# SCH_Workshop-components_2025-10-19_2.net
KiCad netlist of a schematic drawn in EasyEDA
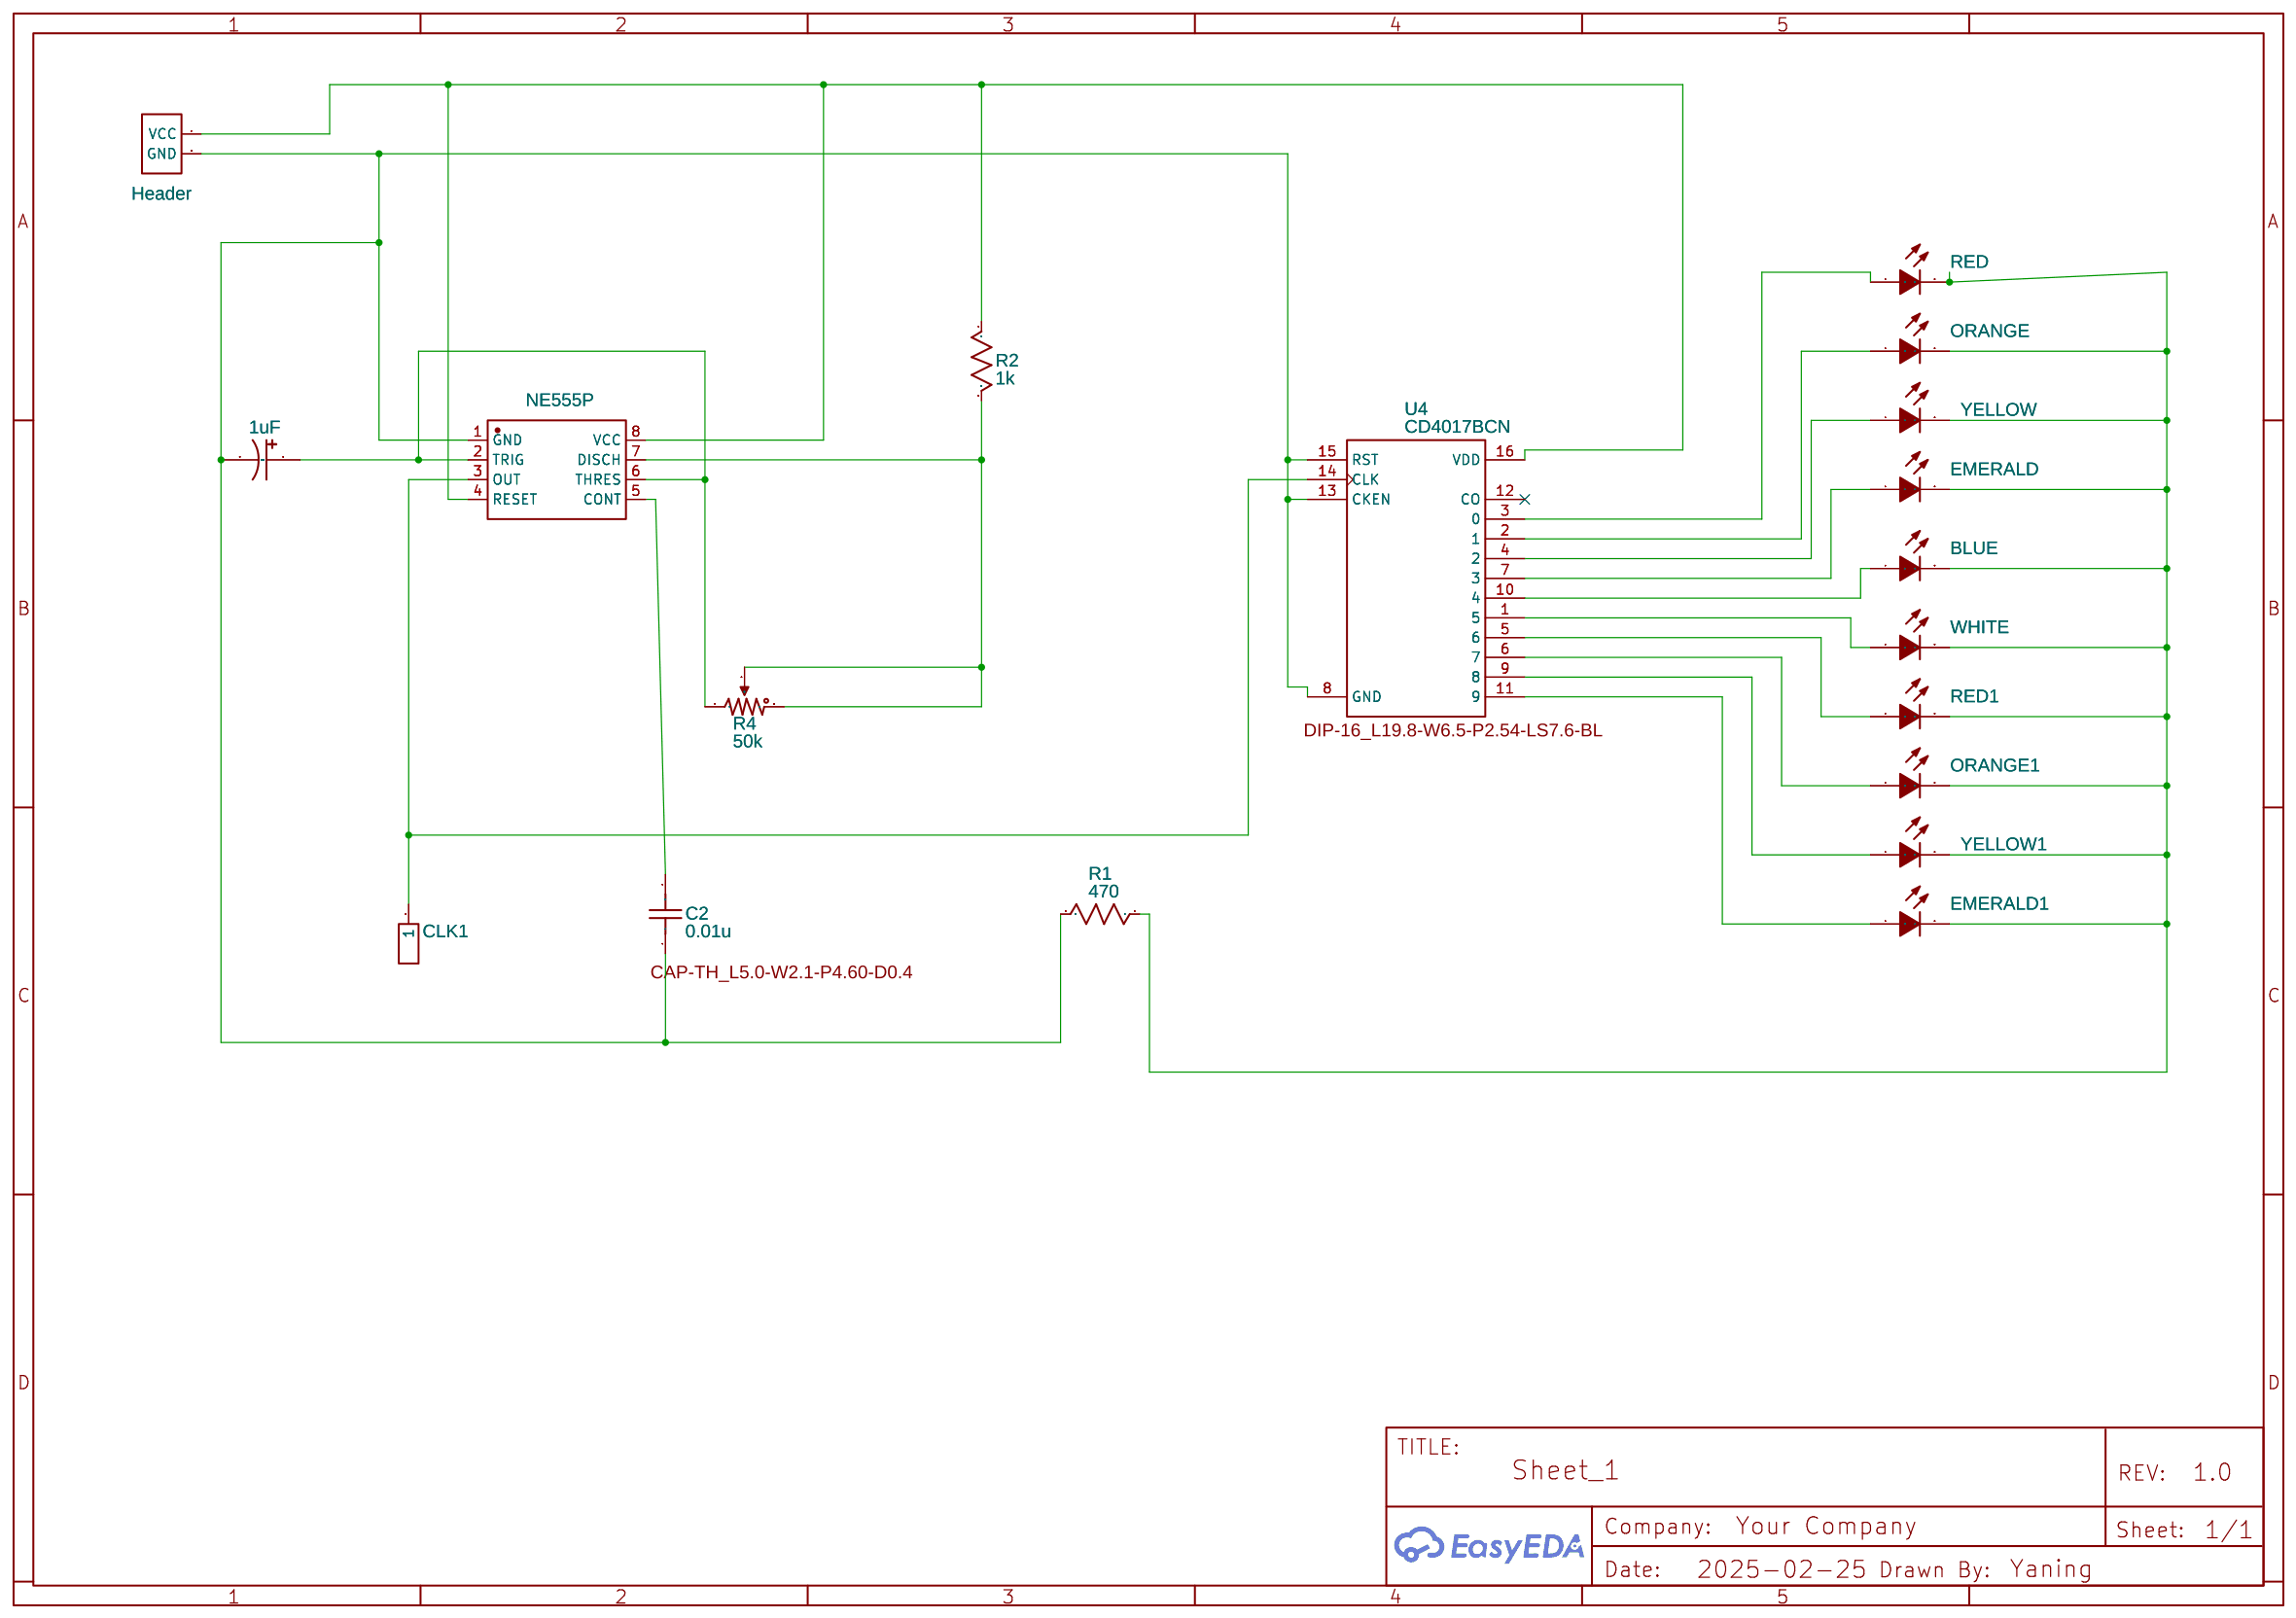
[diagram p0: schematic sheet]

(export (version "E")
  (design (tool "Eeschema 10.0.6"))
  (components
    (comp (ref "BLUE") (value "LED_5MM") (libsource (lib "") (part "LED_5MM")))
    (comp (ref "C1")
      (value "1uF")
      (fields (field (name "Manufacturer Part") "UVZ1H010MDD") (field (name "Manufacturer") "Nichicon(尼吉康)"))
      (libsource (lib "") (part "UVZ1H010MDD"))
    )
    (comp (ref "C2") (value "0.01u") (libsource (lib "") (part "C_0603_US")))
    (comp (ref "CLK1")
      (value "C81276")
      (fields
        (field (name "Manufacturer Part") "2.54-1*1P针")
        (field (name "Manufacturer") "BOOMELE(Boom Precision Elec)")
      )
      (libsource (lib "") (part "Header-Male-2.54_1x1"))
    )
    (comp (ref "EMERALD") (value "LED_5MM") (libsource (lib "") (part "LED_5MM_2")))
    (comp (ref "EMERALD1") (value "LED_5MM") (libsource (lib "") (part "LED_5MM_2")))
    (comp (ref "H1") (value "Header") (libsource (lib "") (part "HEADER-FEMALE-2.54_1X2")))
    (comp (ref "ORANGE") (value "LED_5MM") (libsource (lib "") (part "LED_5MM_3")))
    (comp (ref "ORANGE1") (value "LED_5MM") (libsource (lib "") (part "LED_5MM_3")))
    (comp (ref "R1")
      (value "470")
      (fields (field (name "Manufacturer Part") "?"))
      (libsource (lib "") (part "Resistor"))
    )
    (comp (ref "R2")
      (value "1k")
      (fields (field (name "Manufacturer Part") "?"))
      (libsource (lib "") (part "Resistor_1"))
    )
    (comp (ref "R4")
      (value "50k")
      (fields (field (name "Manufacturer Part") "?"))
      (libsource (lib "") (part "Potentiometer"))
    )
    (comp (ref "RED") (value "LED_5MM") (libsource (lib "") (part "LED_5MM_4")))
    (comp (ref "RED1") (value "LED_5MM") (libsource (lib "") (part "LED_5MM_4")))
    (comp (ref "U2")
      (value "NE555P")
      (fields (field (name "Manufacturer") "TI(德州仪器)"))
      (libsource (lib "") (part "NE555P"))
    )
    (comp (ref "U4") (value "CD4017BCN") (libsource (lib "") (part "CD4017BCN")))
    (comp (ref "WHITE") (value "LED_5MM") (libsource (lib "") (part "LED_5MM_5")))
    (comp (ref "YELLOW") (value "LED_5MM") (libsource (lib "") (part "LED_5MM_1")))
    (comp (ref "YELLOW1") (value "LED_5MM") (libsource (lib "") (part "LED_5MM_1")))
  )
  (nets
    (net (code "1") (name "Net-(BLUE-A)") (class "Default")
      (node (ref "BLUE") (pin "1") (pinfunction "A_1") (pintype "input"))
      (node (ref "U4") (pin "10") (pinfunction "4_10") (pintype "output"))
    )
    (net (code "2") (name "Net-(BLUE-K)") (class "Default")
      (node (ref "BLUE") (pin "2") (pinfunction "K_2") (pintype "input"))
      (node (ref "EMERALD") (pin "2") (pinfunction "K_2") (pintype "input"))
      (node (ref "EMERALD1") (pin "2") (pinfunction "K_2") (pintype "input"))
      (node (ref "ORANGE") (pin "2") (pinfunction "K_2") (pintype "input"))
      (node (ref "ORANGE1") (pin "2") (pinfunction "K_2") (pintype "input"))
      (node (ref "R1") (pin "1") (pinfunction "1_1") (pintype "unspecified"))
      (node (ref "RED") (pin "2") (pinfunction "K_2") (pintype "input"))
      (node (ref "RED1") (pin "2") (pinfunction "K_2") (pintype "input"))
      (node (ref "WHITE") (pin "2") (pinfunction "K_2") (pintype "input"))
      (node (ref "YELLOW") (pin "2") (pinfunction "K_2") (pintype "input"))
      (node (ref "YELLOW1") (pin "2") (pinfunction "K_2") (pintype "input"))
    )
    (net (code "3") (name "Net-(EMERALD-A)") (class "Default")
      (node (ref "EMERALD") (pin "1") (pinfunction "A_1") (pintype "input"))
      (node (ref "U4") (pin "7") (pinfunction "3_7") (pintype "output"))
    )
    (net (code "4") (name "Net-(EMERALD1-A)") (class "Default")
      (node (ref "EMERALD1") (pin "1") (pinfunction "A_1") (pintype "input"))
      (node (ref "U4") (pin "11") (pinfunction "9_11") (pintype "output"))
    )
    (net (code "5") (name "Net-(H1-GND)") (class "Default")
      (node (ref "C1") (pin "2") (pinfunction "2_2") (pintype "unspecified"))
      (node (ref "C2") (pin "1") (pinfunction "1_1") (pintype "unspecified"))
      (node (ref "H1") (pin "2") (pinfunction "GND_2") (pintype "unspecified"))
      (node (ref "R1") (pin "2") (pinfunction "2_2") (pintype "unspecified"))
      (node (ref "U2") (pin "1") (pinfunction "GND_1") (pintype "unspecified"))
      (node (ref "U4") (pin "13") (pinfunction "CKEN_13") (pintype "unspecified"))
      (node (ref "U4") (pin "15") (pinfunction "RST_15") (pintype "unspecified"))
      (node (ref "U4") (pin "8") (pinfunction "GND_8") (pintype "passive"))
    )
    (net (code "6") (name "Net-(H1-VCC)") (class "Default")
      (node (ref "H1") (pin "1") (pinfunction "VCC_1") (pintype "unspecified"))
      (node (ref "R2") (pin "1") (pinfunction "1_1") (pintype "unspecified"))
      (node (ref "U2") (pin "4") (pinfunction "RESET_4") (pintype "unspecified"))
      (node (ref "U2") (pin "8") (pinfunction "VCC_8") (pintype "unspecified"))
      (node (ref "U4") (pin "16") (pinfunction "VDD_16") (pintype "passive"))
    )
    (net (code "7") (name "Net-(ORANGE-A)") (class "Default")
      (node (ref "ORANGE") (pin "1") (pinfunction "A_1") (pintype "input"))
      (node (ref "U4") (pin "2") (pinfunction "1_2") (pintype "output"))
    )
    (net (code "8") (name "Net-(ORANGE1-A)") (class "Default")
      (node (ref "ORANGE1") (pin "1") (pinfunction "A_1") (pintype "input"))
      (node (ref "U4") (pin "6") (pinfunction "7_6") (pintype "output"))
    )
    (net (code "9") (name "Net-(R4-2)") (class "Default")
      (node (ref "R2") (pin "2") (pinfunction "2_2") (pintype "unspecified"))
      (node (ref "R4") (pin "2") (pinfunction "3_2") (pintype "unspecified"))
      (node (ref "R4") (pin "3") (pinfunction "2_3") (pintype "unspecified"))
      (node (ref "U2") (pin "7") (pinfunction "DISCH_7") (pintype "unspecified"))
    )
    (net (code "10") (name "Net-(RED-A)") (class "Default")
      (node (ref "RED") (pin "1") (pinfunction "A_1") (pintype "input"))
      (node (ref "U4") (pin "3") (pinfunction "0_3") (pintype "output"))
    )
    (net (code "11") (name "Net-(RED1-A)") (class "Default")
      (node (ref "RED1") (pin "1") (pinfunction "A_1") (pintype "input"))
      (node (ref "U4") (pin "5") (pinfunction "6_5") (pintype "output"))
    )
    (net (code "12") (name "Net-(U2-CONT)") (class "Default")
      (node (ref "C2") (pin "2") (pinfunction "2_2") (pintype "unspecified"))
      (node (ref "U2") (pin "5") (pinfunction "CONT_5") (pintype "unspecified"))
    )
    (net (code "13") (name "Net-(U2-OUT)") (class "Default")
      (node (ref "CLK1") (pin "1") (pinfunction "1_1") (pintype "unspecified"))
      (node (ref "U2") (pin "3") (pinfunction "OUT_3") (pintype "unspecified"))
      (node (ref "U4") (pin "14") (pinfunction "CLK_14") (pintype "unspecified"))
    )
    (net (code "14") (name "Net-(U2-THRES)") (class "Default")
      (node (ref "C1") (pin "1") (pinfunction "1_1") (pintype "unspecified"))
      (node (ref "R4") (pin "1") (pinfunction "1_1") (pintype "unspecified"))
      (node (ref "U2") (pin "2") (pinfunction "TRIG_2") (pintype "unspecified"))
      (node (ref "U2") (pin "6") (pinfunction "THRES_6") (pintype "unspecified"))
    )
    (net (code "15") (name "Net-(U4-2)") (class "Default")
      (node (ref "U4") (pin "4") (pinfunction "2_4") (pintype "output"))
      (node (ref "YELLOW") (pin "1") (pinfunction "A_1") (pintype "input"))
    )
    (net (code "16") (name "Net-(U4-5)") (class "Default")
      (node (ref "U4") (pin "1") (pinfunction "5_1") (pintype "output"))
      (node (ref "WHITE") (pin "1") (pinfunction "A_1") (pintype "input"))
    )
    (net (code "17") (name "Net-(U4-8)") (class "Default")
      (node (ref "U4") (pin "9") (pinfunction "8_9") (pintype "output"))
      (node (ref "YELLOW1") (pin "1") (pinfunction "A_1") (pintype "input"))
    )
    (net (code "18") (name "unconnected-(U4-CO-Pad12)") (class "Default")
      (node (ref "U4") (pin "12") (pinfunction "CO_12") (pintype "output+no_connect"))
    )
  )
)
